# six2two-switch3-interlock.net
KiCad netlist of a schematic drawn in EAGLE
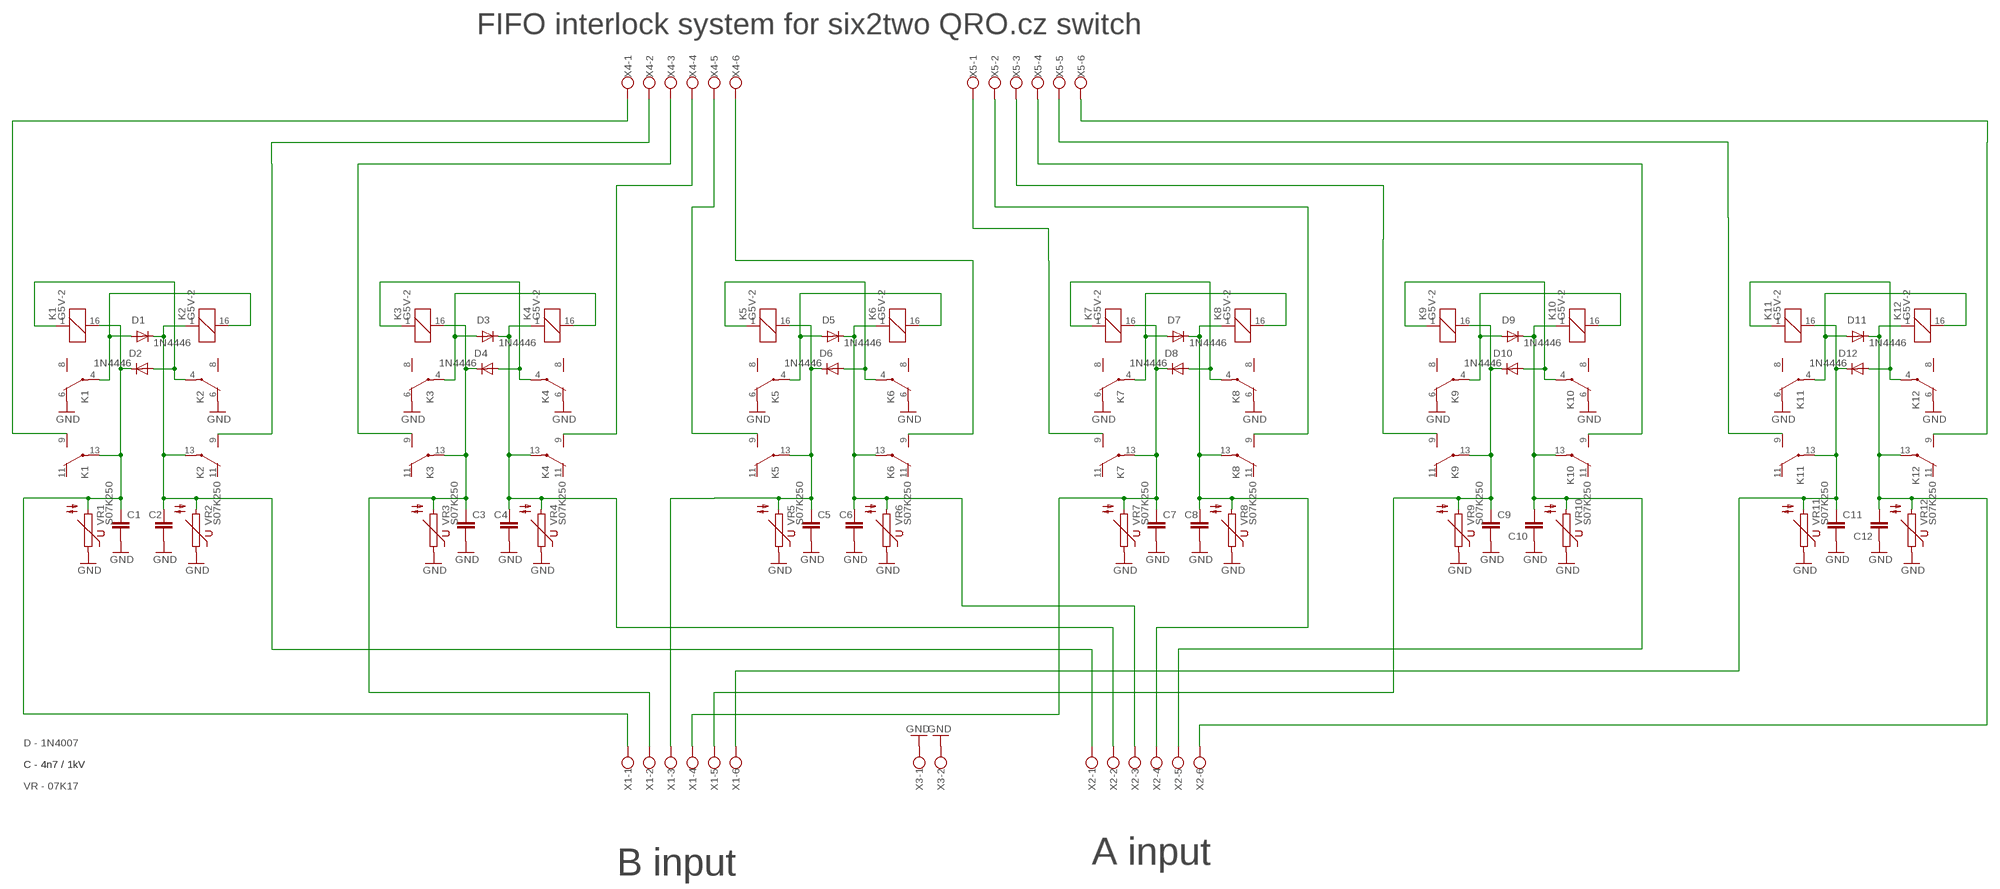
[diagram p0: schematic, sheet 1]

(export (version "E")
  (design (tool "Eeschema 10.0.6"))
  (components
    (comp (ref "C1")
      (value "C-EU050-024X044")
      (footprint "eagle-import:C050-024X044")
      (libsource (lib "eagle-import") (part "C-EU050-024X044"))
    )
    (comp (ref "C2")
      (value "C-EU050-024X044")
      (footprint "eagle-import:C050-024X044")
      (libsource (lib "eagle-import") (part "C-EU050-024X044"))
    )
    (comp (ref "C3")
      (value "C-EU050-024X044")
      (footprint "eagle-import:C050-024X044")
      (libsource (lib "eagle-import") (part "C-EU050-024X044"))
    )
    (comp (ref "C4")
      (value "C-EU050-024X044")
      (footprint "eagle-import:C050-024X044")
      (libsource (lib "eagle-import") (part "C-EU050-024X044"))
    )
    (comp (ref "C5")
      (value "C-EU050-024X044")
      (footprint "eagle-import:C050-024X044")
      (libsource (lib "eagle-import") (part "C-EU050-024X044"))
    )
    (comp (ref "C6")
      (value "C-EU050-024X044")
      (footprint "eagle-import:C050-024X044")
      (libsource (lib "eagle-import") (part "C-EU050-024X044"))
    )
    (comp (ref "C7")
      (value "C-EU050-024X044")
      (footprint "eagle-import:C050-024X044")
      (libsource (lib "eagle-import") (part "C-EU050-024X044"))
    )
    (comp (ref "C8")
      (value "C-EU050-024X044")
      (footprint "eagle-import:C050-024X044")
      (libsource (lib "eagle-import") (part "C-EU050-024X044"))
    )
    (comp (ref "C9")
      (value "C-EU050-024X044")
      (footprint "eagle-import:C050-024X044")
      (libsource (lib "eagle-import") (part "C-EU050-024X044"))
    )
    (comp (ref "C10")
      (value "C-EU050-024X044")
      (footprint "eagle-import:C050-024X044")
      (libsource (lib "eagle-import") (part "C-EU050-024X044"))
    )
    (comp (ref "C11")
      (value "C-EU050-024X044")
      (footprint "eagle-import:C050-024X044")
      (libsource (lib "eagle-import") (part "C-EU050-024X044"))
    )
    (comp (ref "C12")
      (value "C-EU050-024X044")
      (footprint "eagle-import:C050-024X044")
      (libsource (lib "eagle-import") (part "C-EU050-024X044"))
    )
    (comp (ref "D1")
      (value "1N4446")
      (footprint "eagle-import:DO35-10")
      (libsource (lib "eagle-import") (part "1N4446"))
    )
    (comp (ref "D2")
      (value "1N4446")
      (footprint "eagle-import:DO35-10")
      (libsource (lib "eagle-import") (part "1N4446"))
    )
    (comp (ref "D3")
      (value "1N4446")
      (footprint "eagle-import:DO35-10")
      (libsource (lib "eagle-import") (part "1N4446"))
    )
    (comp (ref "D4")
      (value "1N4446")
      (footprint "eagle-import:DO35-10")
      (libsource (lib "eagle-import") (part "1N4446"))
    )
    (comp (ref "D5")
      (value "1N4446")
      (footprint "eagle-import:DO35-10")
      (libsource (lib "eagle-import") (part "1N4446"))
    )
    (comp (ref "D6")
      (value "1N4446")
      (footprint "eagle-import:DO35-10")
      (libsource (lib "eagle-import") (part "1N4446"))
    )
    (comp (ref "D7")
      (value "1N4446")
      (footprint "eagle-import:DO35-10")
      (libsource (lib "eagle-import") (part "1N4446"))
    )
    (comp (ref "D8")
      (value "1N4446")
      (footprint "eagle-import:DO35-10")
      (libsource (lib "eagle-import") (part "1N4446"))
    )
    (comp (ref "D9")
      (value "1N4446")
      (footprint "eagle-import:DO35-10")
      (libsource (lib "eagle-import") (part "1N4446"))
    )
    (comp (ref "D10")
      (value "1N4446")
      (footprint "eagle-import:DO35-10")
      (libsource (lib "eagle-import") (part "1N4446"))
    )
    (comp (ref "D11")
      (value "1N4446")
      (footprint "eagle-import:DO35-10")
      (libsource (lib "eagle-import") (part "1N4446"))
    )
    (comp (ref "D12")
      (value "1N4446")
      (footprint "eagle-import:DO35-10")
      (libsource (lib "eagle-import") (part "1N4446"))
    )
    (comp (ref "K1")
      (value "G5V-2")
      (footprint "eagle-import:G5V-2")
      (fields (field (name "MPN") "G5V-2 5DC"))
      (libsource (lib "eagle-import") (part "G5V-2"))
    )
    (comp (ref "K2")
      (value "G5V-2")
      (footprint "eagle-import:G5V-2")
      (fields (field (name "MPN") "G5V-2 5DC"))
      (libsource (lib "eagle-import") (part "G5V-2"))
    )
    (comp (ref "K3")
      (value "G5V-2")
      (footprint "eagle-import:G5V-2")
      (fields (field (name "MPN") "G5V-2 5DC"))
      (libsource (lib "eagle-import") (part "G5V-2"))
    )
    (comp (ref "K4")
      (value "G5V-2")
      (footprint "eagle-import:G5V-2")
      (fields (field (name "MPN") "G5V-2 5DC"))
      (libsource (lib "eagle-import") (part "G5V-2"))
    )
    (comp (ref "K5")
      (value "G5V-2")
      (footprint "eagle-import:G5V-2")
      (fields (field (name "MPN") "G5V-2 5DC"))
      (libsource (lib "eagle-import") (part "G5V-2"))
    )
    (comp (ref "K6")
      (value "G5V-2")
      (footprint "eagle-import:G5V-2")
      (fields (field (name "MPN") "G5V-2 5DC"))
      (libsource (lib "eagle-import") (part "G5V-2"))
    )
    (comp (ref "K7")
      (value "G5V-2")
      (footprint "eagle-import:G5V-2")
      (fields (field (name "MPN") "G5V-2 5DC"))
      (libsource (lib "eagle-import") (part "G5V-2"))
    )
    (comp (ref "K8")
      (value "G5V-2")
      (footprint "eagle-import:G5V-2")
      (fields (field (name "MPN") "G5V-2 5DC"))
      (libsource (lib "eagle-import") (part "G5V-2"))
    )
    (comp (ref "K9")
      (value "G5V-2")
      (footprint "eagle-import:G5V-2")
      (fields (field (name "MPN") "G5V-2 5DC"))
      (libsource (lib "eagle-import") (part "G5V-2"))
    )
    (comp (ref "K10")
      (value "G5V-2")
      (footprint "eagle-import:G5V-2")
      (fields (field (name "MPN") "G5V-2 5DC"))
      (libsource (lib "eagle-import") (part "G5V-2"))
    )
    (comp (ref "K11")
      (value "G5V-2")
      (footprint "eagle-import:G5V-2")
      (fields (field (name "MPN") "G5V-2 5DC"))
      (libsource (lib "eagle-import") (part "G5V-2"))
    )
    (comp (ref "K12")
      (value "G5V-2")
      (footprint "eagle-import:G5V-2")
      (fields (field (name "MPN") "G5V-2 5DC"))
      (libsource (lib "eagle-import") (part "G5V-2"))
    )
    (comp (ref "VR1")
      (value "S07K250")
      (footprint "eagle-import:S07K250")
      (libsource (lib "eagle-import") (part "S07K250"))
    )
    (comp (ref "VR2")
      (value "S07K250")
      (footprint "eagle-import:S07K250")
      (libsource (lib "eagle-import") (part "S07K250"))
    )
    (comp (ref "VR3")
      (value "S07K250")
      (footprint "eagle-import:S07K250")
      (libsource (lib "eagle-import") (part "S07K250"))
    )
    (comp (ref "VR4")
      (value "S07K250")
      (footprint "eagle-import:S07K250")
      (libsource (lib "eagle-import") (part "S07K250"))
    )
    (comp (ref "VR5")
      (value "S07K250")
      (footprint "eagle-import:S07K250")
      (libsource (lib "eagle-import") (part "S07K250"))
    )
    (comp (ref "VR6")
      (value "S07K250")
      (footprint "eagle-import:S07K250")
      (libsource (lib "eagle-import") (part "S07K250"))
    )
    (comp (ref "VR7")
      (value "S07K250")
      (footprint "eagle-import:S07K250")
      (libsource (lib "eagle-import") (part "S07K250"))
    )
    (comp (ref "VR8")
      (value "S07K250")
      (footprint "eagle-import:S07K250")
      (libsource (lib "eagle-import") (part "S07K250"))
    )
    (comp (ref "VR9")
      (value "S07K250")
      (footprint "eagle-import:S07K250")
      (libsource (lib "eagle-import") (part "S07K250"))
    )
    (comp (ref "VR10")
      (value "S07K250")
      (footprint "eagle-import:S07K250")
      (libsource (lib "eagle-import") (part "S07K250"))
    )
    (comp (ref "VR11")
      (value "S07K250")
      (footprint "eagle-import:S07K250")
      (libsource (lib "eagle-import") (part "S07K250"))
    )
    (comp (ref "VR12")
      (value "S07K250")
      (footprint "eagle-import:S07K250")
      (libsource (lib "eagle-import") (part "S07K250"))
    )
    (comp (ref "X1")
      (value "W237-136")
      (footprint "eagle-import:W237-136")
      (fields (field (name "MPN") "237-136"))
      (libsource (lib "eagle-import") (part "W237-136"))
    )
    (comp (ref "X2")
      (value "W237-136")
      (footprint "eagle-import:W237-136")
      (fields (field (name "MPN") "237-136"))
      (libsource (lib "eagle-import") (part "W237-136"))
    )
    (comp (ref "X3")
      (value "W237-102")
      (footprint "eagle-import:W237-102")
      (fields (field (name "MPN") "237-102"))
      (libsource (lib "eagle-import") (part "W237-102"))
    )
    (comp (ref "X4")
      (value "W237-136")
      (footprint "eagle-import:W237-136")
      (fields (field (name "MPN") "237-136"))
      (libsource (lib "eagle-import") (part "W237-136"))
    )
    (comp (ref "X5")
      (value "W237-136")
      (footprint "eagle-import:W237-136")
      (fields (field (name "MPN") "237-136"))
      (libsource (lib "eagle-import") (part "W237-136"))
    )
  )
  (nets
    (net (code "1") (name "GND") (class "Default")
      (node (ref "C1") (pin "2") (pinfunction "2_2") (pintype "passive"))
      (node (ref "C10") (pin "2") (pinfunction "2_2") (pintype "passive"))
      (node (ref "C11") (pin "2") (pinfunction "2_2") (pintype "passive"))
      (node (ref "C12") (pin "2") (pinfunction "2_2") (pintype "passive"))
      (node (ref "C2") (pin "2") (pinfunction "2_2") (pintype "passive"))
      (node (ref "C3") (pin "2") (pinfunction "2_2") (pintype "passive"))
      (node (ref "C4") (pin "2") (pinfunction "2_2") (pintype "passive"))
      (node (ref "C5") (pin "2") (pinfunction "2_2") (pintype "passive"))
      (node (ref "C6") (pin "2") (pinfunction "2_2") (pintype "passive"))
      (node (ref "C7") (pin "2") (pinfunction "2_2") (pintype "passive"))
      (node (ref "C8") (pin "2") (pinfunction "2_2") (pintype "passive"))
      (node (ref "C9") (pin "2") (pinfunction "2_2") (pintype "passive"))
      (node (ref "K1") (pin "6") (pinfunction "O_6") (pintype "passive"))
      (node (ref "K10") (pin "6") (pinfunction "O_6") (pintype "passive"))
      (node (ref "K11") (pin "6") (pinfunction "O_6") (pintype "passive"))
      (node (ref "K12") (pin "6") (pinfunction "O_6") (pintype "passive"))
      (node (ref "K2") (pin "6") (pinfunction "O_6") (pintype "passive"))
      (node (ref "K3") (pin "6") (pinfunction "O_6") (pintype "passive"))
      (node (ref "K4") (pin "6") (pinfunction "O_6") (pintype "passive"))
      (node (ref "K5") (pin "6") (pinfunction "O_6") (pintype "passive"))
      (node (ref "K6") (pin "6") (pinfunction "O_6") (pintype "passive"))
      (node (ref "K7") (pin "6") (pinfunction "O_6") (pintype "passive"))
      (node (ref "K8") (pin "6") (pinfunction "O_6") (pintype "passive"))
      (node (ref "K9") (pin "6") (pinfunction "O_6") (pintype "passive"))
      (node (ref "VR1") (pin "1") (pinfunction "1_1") (pintype "passive"))
      (node (ref "VR10") (pin "1") (pinfunction "1_1") (pintype "passive"))
      (node (ref "VR11") (pin "1") (pinfunction "1_1") (pintype "passive"))
      (node (ref "VR12") (pin "1") (pinfunction "1_1") (pintype "passive"))
      (node (ref "VR2") (pin "1") (pinfunction "1_1") (pintype "passive"))
      (node (ref "VR3") (pin "1") (pinfunction "1_1") (pintype "passive"))
      (node (ref "VR4") (pin "1") (pinfunction "1_1") (pintype "passive"))
      (node (ref "VR5") (pin "1") (pinfunction "1_1") (pintype "passive"))
      (node (ref "VR6") (pin "1") (pinfunction "1_1") (pintype "passive"))
      (node (ref "VR7") (pin "1") (pinfunction "1_1") (pintype "passive"))
      (node (ref "VR8") (pin "1") (pinfunction "1_1") (pintype "passive"))
      (node (ref "VR9") (pin "1") (pinfunction "1_1") (pintype "passive"))
      (node (ref "X3") (pin "1") (pinfunction "KL_1") (pintype "passive"))
      (node (ref "X3") (pin "2") (pinfunction "KL_2") (pintype "passive"))
    )
    (net (code "2") (name "Net-(K1A-P)") (class "Default")
      (node (ref "D1") (pin "A") (pinfunction "A_A") (pintype "passive"))
      (node (ref "K1") (pin "4") (pinfunction "P_4") (pintype "passive"))
      (node (ref "K2") (pin "16") (pinfunction "2_16") (pintype "passive"))
    )
    (net (code "3") (name "Net-(K1B-P)") (class "Default")
      (node (ref "C1") (pin "1") (pinfunction "1_1") (pintype "passive"))
      (node (ref "D2") (pin "C") (pinfunction "C_C") (pintype "passive"))
      (node (ref "K1") (pin "13") (pinfunction "P_13") (pintype "passive"))
      (node (ref "K1") (pin "16") (pinfunction "2_16") (pintype "passive"))
      (node (ref "VR1") (pin "2") (pinfunction "2_2") (pintype "passive"))
      (node (ref "X1") (pin "1") (pinfunction "KL_1") (pintype "passive"))
    )
    (net (code "4") (name "Net-(K1B-S)") (class "Default")
      (node (ref "K1") (pin "9") (pinfunction "S_9") (pintype "passive"))
      (node (ref "X4") (pin "1") (pinfunction "KL_1") (pintype "passive"))
    )
    (net (code "5") (name "Net-(K2A-P)") (class "Default")
      (node (ref "D2") (pin "A") (pinfunction "A_A") (pintype "passive"))
      (node (ref "K1") (pin "1") (pinfunction "1_1") (pintype "passive"))
      (node (ref "K2") (pin "4") (pinfunction "P_4") (pintype "passive"))
    )
    (net (code "6") (name "Net-(K2B-P)") (class "Default")
      (node (ref "C2") (pin "1") (pinfunction "1_1") (pintype "passive"))
      (node (ref "D1") (pin "C") (pinfunction "C_C") (pintype "passive"))
      (node (ref "K2") (pin "1") (pinfunction "1_1") (pintype "passive"))
      (node (ref "K2") (pin "13") (pinfunction "P_13") (pintype "passive"))
      (node (ref "VR2") (pin "2") (pinfunction "2_2") (pintype "passive"))
      (node (ref "X2") (pin "1") (pinfunction "KL_1") (pintype "passive"))
    )
    (net (code "7") (name "Net-(K2B-S)") (class "Default")
      (node (ref "K2") (pin "9") (pinfunction "S_9") (pintype "passive"))
      (node (ref "X4") (pin "2") (pinfunction "KL_2") (pintype "passive"))
    )
    (net (code "8") (name "Net-(K3A-P)") (class "Default")
      (node (ref "D3") (pin "A") (pinfunction "A_A") (pintype "passive"))
      (node (ref "K3") (pin "4") (pinfunction "P_4") (pintype "passive"))
      (node (ref "K4") (pin "16") (pinfunction "2_16") (pintype "passive"))
    )
    (net (code "9") (name "Net-(K3B-P)") (class "Default")
      (node (ref "C3") (pin "1") (pinfunction "1_1") (pintype "passive"))
      (node (ref "D4") (pin "C") (pinfunction "C_C") (pintype "passive"))
      (node (ref "K3") (pin "13") (pinfunction "P_13") (pintype "passive"))
      (node (ref "K3") (pin "16") (pinfunction "2_16") (pintype "passive"))
      (node (ref "VR3") (pin "2") (pinfunction "2_2") (pintype "passive"))
      (node (ref "X1") (pin "2") (pinfunction "KL_2") (pintype "passive"))
    )
    (net (code "10") (name "Net-(K3B-S)") (class "Default")
      (node (ref "K3") (pin "9") (pinfunction "S_9") (pintype "passive"))
      (node (ref "X4") (pin "3") (pinfunction "KL_3") (pintype "passive"))
    )
    (net (code "11") (name "Net-(K4A-P)") (class "Default")
      (node (ref "D4") (pin "A") (pinfunction "A_A") (pintype "passive"))
      (node (ref "K3") (pin "1") (pinfunction "1_1") (pintype "passive"))
      (node (ref "K4") (pin "4") (pinfunction "P_4") (pintype "passive"))
    )
    (net (code "12") (name "Net-(K4B-P)") (class "Default")
      (node (ref "C4") (pin "1") (pinfunction "1_1") (pintype "passive"))
      (node (ref "D3") (pin "C") (pinfunction "C_C") (pintype "passive"))
      (node (ref "K4") (pin "1") (pinfunction "1_1") (pintype "passive"))
      (node (ref "K4") (pin "13") (pinfunction "P_13") (pintype "passive"))
      (node (ref "VR4") (pin "2") (pinfunction "2_2") (pintype "passive"))
      (node (ref "X2") (pin "2") (pinfunction "KL_2") (pintype "passive"))
    )
    (net (code "13") (name "Net-(K4B-S)") (class "Default")
      (node (ref "K4") (pin "9") (pinfunction "S_9") (pintype "passive"))
      (node (ref "X4") (pin "4") (pinfunction "KL_4") (pintype "passive"))
    )
    (net (code "14") (name "Net-(K5A-P)") (class "Default")
      (node (ref "D5") (pin "A") (pinfunction "A_A") (pintype "passive"))
      (node (ref "K5") (pin "4") (pinfunction "P_4") (pintype "passive"))
      (node (ref "K6") (pin "16") (pinfunction "2_16") (pintype "passive"))
    )
    (net (code "15") (name "Net-(K5B-P)") (class "Default")
      (node (ref "C5") (pin "1") (pinfunction "1_1") (pintype "passive"))
      (node (ref "D6") (pin "C") (pinfunction "C_C") (pintype "passive"))
      (node (ref "K5") (pin "13") (pinfunction "P_13") (pintype "passive"))
      (node (ref "K5") (pin "16") (pinfunction "2_16") (pintype "passive"))
      (node (ref "VR5") (pin "2") (pinfunction "2_2") (pintype "passive"))
      (node (ref "X1") (pin "3") (pinfunction "KL_3") (pintype "passive"))
    )
    (net (code "16") (name "Net-(K5B-S)") (class "Default")
      (node (ref "K5") (pin "9") (pinfunction "S_9") (pintype "passive"))
      (node (ref "X4") (pin "5") (pinfunction "KL_5") (pintype "passive"))
    )
    (net (code "17") (name "Net-(K6A-P)") (class "Default")
      (node (ref "D6") (pin "A") (pinfunction "A_A") (pintype "passive"))
      (node (ref "K5") (pin "1") (pinfunction "1_1") (pintype "passive"))
      (node (ref "K6") (pin "4") (pinfunction "P_4") (pintype "passive"))
    )
    (net (code "18") (name "Net-(K6B-P)") (class "Default")
      (node (ref "C6") (pin "1") (pinfunction "1_1") (pintype "passive"))
      (node (ref "D5") (pin "C") (pinfunction "C_C") (pintype "passive"))
      (node (ref "K6") (pin "1") (pinfunction "1_1") (pintype "passive"))
      (node (ref "K6") (pin "13") (pinfunction "P_13") (pintype "passive"))
      (node (ref "VR6") (pin "2") (pinfunction "2_2") (pintype "passive"))
      (node (ref "X2") (pin "3") (pinfunction "KL_3") (pintype "passive"))
    )
    (net (code "19") (name "Net-(K6B-S)") (class "Default")
      (node (ref "K6") (pin "9") (pinfunction "S_9") (pintype "passive"))
      (node (ref "X4") (pin "6") (pinfunction "KL_6") (pintype "passive"))
    )
    (net (code "20") (name "Net-(K7A-P)") (class "Default")
      (node (ref "D7") (pin "A") (pinfunction "A_A") (pintype "passive"))
      (node (ref "K7") (pin "4") (pinfunction "P_4") (pintype "passive"))
      (node (ref "K8") (pin "16") (pinfunction "2_16") (pintype "passive"))
    )
    (net (code "21") (name "Net-(K7B-P)") (class "Default")
      (node (ref "C7") (pin "1") (pinfunction "1_1") (pintype "passive"))
      (node (ref "D8") (pin "C") (pinfunction "C_C") (pintype "passive"))
      (node (ref "K7") (pin "13") (pinfunction "P_13") (pintype "passive"))
      (node (ref "K7") (pin "16") (pinfunction "2_16") (pintype "passive"))
      (node (ref "VR7") (pin "2") (pinfunction "2_2") (pintype "passive"))
      (node (ref "X1") (pin "4") (pinfunction "KL_4") (pintype "passive"))
    )
    (net (code "22") (name "Net-(K7B-S)") (class "Default")
      (node (ref "K7") (pin "9") (pinfunction "S_9") (pintype "passive"))
      (node (ref "X5") (pin "1") (pinfunction "KL_1") (pintype "passive"))
    )
    (net (code "23") (name "Net-(K8A-P)") (class "Default")
      (node (ref "D8") (pin "A") (pinfunction "A_A") (pintype "passive"))
      (node (ref "K7") (pin "1") (pinfunction "1_1") (pintype "passive"))
      (node (ref "K8") (pin "4") (pinfunction "P_4") (pintype "passive"))
    )
    (net (code "24") (name "Net-(K8B-P)") (class "Default")
      (node (ref "C8") (pin "1") (pinfunction "1_1") (pintype "passive"))
      (node (ref "D7") (pin "C") (pinfunction "C_C") (pintype "passive"))
      (node (ref "K8") (pin "1") (pinfunction "1_1") (pintype "passive"))
      (node (ref "K8") (pin "13") (pinfunction "P_13") (pintype "passive"))
      (node (ref "VR8") (pin "2") (pinfunction "2_2") (pintype "passive"))
      (node (ref "X2") (pin "4") (pinfunction "KL_4") (pintype "passive"))
    )
    (net (code "25") (name "Net-(K8B-S)") (class "Default")
      (node (ref "K8") (pin "9") (pinfunction "S_9") (pintype "passive"))
      (node (ref "X5") (pin "2") (pinfunction "KL_2") (pintype "passive"))
    )
    (net (code "26") (name "Net-(K9B-P)") (class "Default")
      (node (ref "C9") (pin "1") (pinfunction "1_1") (pintype "passive"))
      (node (ref "D10") (pin "C") (pinfunction "C_C") (pintype "passive"))
      (node (ref "K9") (pin "13") (pinfunction "P_13") (pintype "passive"))
      (node (ref "K9") (pin "16") (pinfunction "2_16") (pintype "passive"))
      (node (ref "VR9") (pin "2") (pinfunction "2_2") (pintype "passive"))
      (node (ref "X1") (pin "5") (pinfunction "KL_5") (pintype "passive"))
    )
    (net (code "27") (name "Net-(K9B-S)") (class "Default")
      (node (ref "K9") (pin "9") (pinfunction "S_9") (pintype "passive"))
      (node (ref "X5") (pin "3") (pinfunction "KL_3") (pintype "passive"))
    )
    (net (code "28") (name "Net-(K10A-P)") (class "Default")
      (node (ref "D10") (pin "A") (pinfunction "A_A") (pintype "passive"))
      (node (ref "K10") (pin "4") (pinfunction "P_4") (pintype "passive"))
      (node (ref "K9") (pin "1") (pinfunction "1_1") (pintype "passive"))
    )
    (net (code "29") (name "Net-(K10B-P)") (class "Default")
      (node (ref "C10") (pin "1") (pinfunction "1_1") (pintype "passive"))
      (node (ref "D9") (pin "C") (pinfunction "C_C") (pintype "passive"))
      (node (ref "K10") (pin "1") (pinfunction "1_1") (pintype "passive"))
      (node (ref "K10") (pin "13") (pinfunction "P_13") (pintype "passive"))
      (node (ref "VR10") (pin "2") (pinfunction "2_2") (pintype "passive"))
      (node (ref "X2") (pin "5") (pinfunction "KL_5") (pintype "passive"))
    )
    (net (code "30") (name "Net-(K10B-S)") (class "Default")
      (node (ref "K10") (pin "9") (pinfunction "S_9") (pintype "passive"))
      (node (ref "X5") (pin "4") (pinfunction "KL_4") (pintype "passive"))
    )
    (net (code "31") (name "Net-(K10C-2)") (class "Default")
      (node (ref "D9") (pin "A") (pinfunction "A_A") (pintype "passive"))
      (node (ref "K10") (pin "16") (pinfunction "2_16") (pintype "passive"))
      (node (ref "K9") (pin "4") (pinfunction "P_4") (pintype "passive"))
    )
    (net (code "32") (name "Net-(K11A-P)") (class "Default")
      (node (ref "D11") (pin "A") (pinfunction "A_A") (pintype "passive"))
      (node (ref "K11") (pin "4") (pinfunction "P_4") (pintype "passive"))
      (node (ref "K12") (pin "16") (pinfunction "2_16") (pintype "passive"))
    )
    (net (code "33") (name "Net-(K11B-P)") (class "Default")
      (node (ref "C11") (pin "1") (pinfunction "1_1") (pintype "passive"))
      (node (ref "D12") (pin "C") (pinfunction "C_C") (pintype "passive"))
      (node (ref "K11") (pin "13") (pinfunction "P_13") (pintype "passive"))
      (node (ref "K11") (pin "16") (pinfunction "2_16") (pintype "passive"))
      (node (ref "VR11") (pin "2") (pinfunction "2_2") (pintype "passive"))
      (node (ref "X1") (pin "6") (pinfunction "KL_6") (pintype "passive"))
    )
    (net (code "34") (name "Net-(K11B-S)") (class "Default")
      (node (ref "K11") (pin "9") (pinfunction "S_9") (pintype "passive"))
      (node (ref "X5") (pin "5") (pinfunction "KL_5") (pintype "passive"))
    )
    (net (code "35") (name "Net-(K12A-P)") (class "Default")
      (node (ref "D12") (pin "A") (pinfunction "A_A") (pintype "passive"))
      (node (ref "K11") (pin "1") (pinfunction "1_1") (pintype "passive"))
      (node (ref "K12") (pin "4") (pinfunction "P_4") (pintype "passive"))
    )
    (net (code "36") (name "Net-(K12B-P)") (class "Default")
      (node (ref "C12") (pin "1") (pinfunction "1_1") (pintype "passive"))
      (node (ref "D11") (pin "C") (pinfunction "C_C") (pintype "passive"))
      (node (ref "K12") (pin "1") (pinfunction "1_1") (pintype "passive"))
      (node (ref "K12") (pin "13") (pinfunction "P_13") (pintype "passive"))
      (node (ref "VR12") (pin "2") (pinfunction "2_2") (pintype "passive"))
      (node (ref "X2") (pin "6") (pinfunction "KL_6") (pintype "passive"))
    )
    (net (code "37") (name "Net-(K12B-S)") (class "Default")
      (node (ref "K12") (pin "9") (pinfunction "S_9") (pintype "passive"))
      (node (ref "X5") (pin "6") (pinfunction "KL_6") (pintype "passive"))
    )
    (net (code "38") (name "unconnected-(K1A-S-Pad8)") (class "Default")
      (node (ref "K1") (pin "8") (pinfunction "S_8") (pintype "passive"))
    )
    (net (code "39") (name "unconnected-(K1B-O-Pad11)") (class "Default")
      (node (ref "K1") (pin "11") (pinfunction "O_11") (pintype "passive"))
    )
    (net (code "40") (name "unconnected-(K2A-S-Pad8)") (class "Default")
      (node (ref "K2") (pin "8") (pinfunction "S_8") (pintype "passive"))
    )
    (net (code "41") (name "unconnected-(K2B-O-Pad11)") (class "Default")
      (node (ref "K2") (pin "11") (pinfunction "O_11") (pintype "passive"))
    )
    (net (code "42") (name "unconnected-(K3A-S-Pad8)") (class "Default")
      (node (ref "K3") (pin "8") (pinfunction "S_8") (pintype "passive"))
    )
    (net (code "43") (name "unconnected-(K3B-O-Pad11)") (class "Default")
      (node (ref "K3") (pin "11") (pinfunction "O_11") (pintype "passive"))
    )
    (net (code "44") (name "unconnected-(K4A-S-Pad8)") (class "Default")
      (node (ref "K4") (pin "8") (pinfunction "S_8") (pintype "passive"))
    )
    (net (code "45") (name "unconnected-(K4B-O-Pad11)") (class "Default")
      (node (ref "K4") (pin "11") (pinfunction "O_11") (pintype "passive"))
    )
    (net (code "46") (name "unconnected-(K5A-S-Pad8)") (class "Default")
      (node (ref "K5") (pin "8") (pinfunction "S_8") (pintype "passive"))
    )
    (net (code "47") (name "unconnected-(K5B-O-Pad11)") (class "Default")
      (node (ref "K5") (pin "11") (pinfunction "O_11") (pintype "passive"))
    )
    (net (code "48") (name "unconnected-(K6A-S-Pad8)") (class "Default")
      (node (ref "K6") (pin "8") (pinfunction "S_8") (pintype "passive"))
    )
    (net (code "49") (name "unconnected-(K6B-O-Pad11)") (class "Default")
      (node (ref "K6") (pin "11") (pinfunction "O_11") (pintype "passive"))
    )
    (net (code "50") (name "unconnected-(K7A-S-Pad8)") (class "Default")
      (node (ref "K7") (pin "8") (pinfunction "S_8") (pintype "passive"))
    )
    (net (code "51") (name "unconnected-(K7B-O-Pad11)") (class "Default")
      (node (ref "K7") (pin "11") (pinfunction "O_11") (pintype "passive"))
    )
    (net (code "52") (name "unconnected-(K8A-S-Pad8)") (class "Default")
      (node (ref "K8") (pin "8") (pinfunction "S_8") (pintype "passive"))
    )
    (net (code "53") (name "unconnected-(K8B-O-Pad11)") (class "Default")
      (node (ref "K8") (pin "11") (pinfunction "O_11") (pintype "passive"))
    )
    (net (code "54") (name "unconnected-(K9A-S-Pad8)") (class "Default")
      (node (ref "K9") (pin "8") (pinfunction "S_8") (pintype "passive"))
    )
    (net (code "55") (name "unconnected-(K9B-O-Pad11)") (class "Default")
      (node (ref "K9") (pin "11") (pinfunction "O_11") (pintype "passive"))
    )
    (net (code "56") (name "unconnected-(K10A-S-Pad8)") (class "Default")
      (node (ref "K10") (pin "8") (pinfunction "S_8") (pintype "passive"))
    )
    (net (code "57") (name "unconnected-(K10B-O-Pad11)") (class "Default")
      (node (ref "K10") (pin "11") (pinfunction "O_11") (pintype "passive"))
    )
    (net (code "58") (name "unconnected-(K11A-S-Pad8)") (class "Default")
      (node (ref "K11") (pin "8") (pinfunction "S_8") (pintype "passive"))
    )
    (net (code "59") (name "unconnected-(K11B-O-Pad11)") (class "Default")
      (node (ref "K11") (pin "11") (pinfunction "O_11") (pintype "passive"))
    )
    (net (code "60") (name "unconnected-(K12A-S-Pad8)") (class "Default")
      (node (ref "K12") (pin "8") (pinfunction "S_8") (pintype "passive"))
    )
    (net (code "61") (name "unconnected-(K12B-O-Pad11)") (class "Default")
      (node (ref "K12") (pin "11") (pinfunction "O_11") (pintype "passive"))
    )
  )
)
